# TOP.net
KiCad netlist of a schematic drawn in Altium Designer
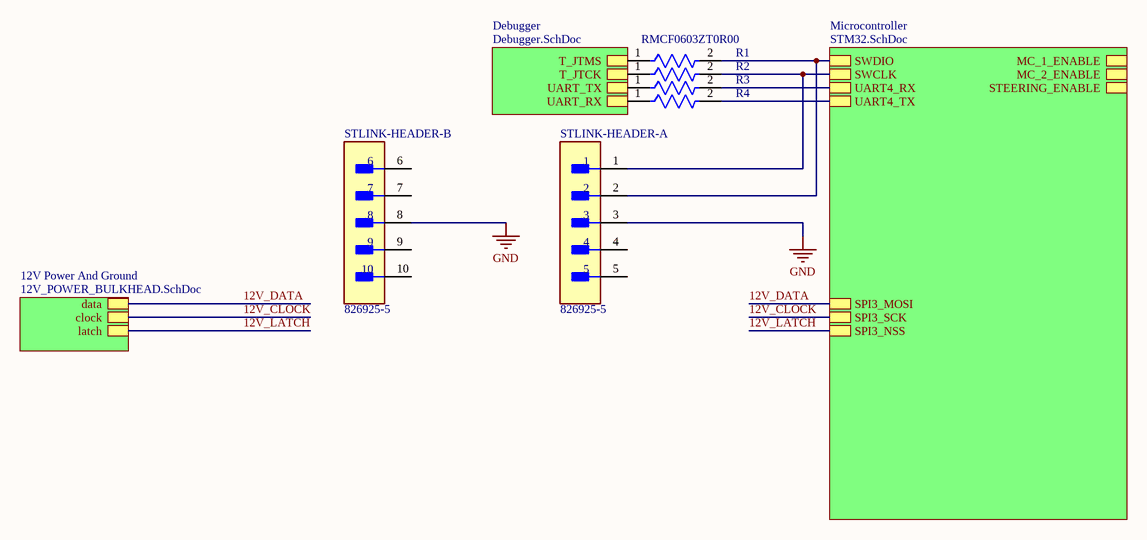
[diagram p0: TOP.SchDoc]

(export (version "E")
  (design (tool "Eeschema 10.0.6"))
  (components
    (comp (ref "R1")
      (value "RMCF0603ZT0R00")
      (footprint "FP-RMCF0603-MFG")
      (description "RES 0 OHM JUMPER 1/10W 0603")
      (fields
        (field (name "OCTOPART") "https://octopart.com/rmcf0603zt0r00-stackpole+electronics-19213618")
        (field (name "MANUFACTURER") "Stackpole")
      )
      (libsource (lib "Altium Content Vault") (part "1029c3af85768c4190bb7ad29bc67b5"))
    )
    (comp (ref "R2")
      (value "RMCF0603ZT0R00")
      (footprint "FP-RMCF0603-MFG")
      (description "RES 0 OHM JUMPER 1/10W 0603")
      (fields
        (field (name "OCTOPART") "https://octopart.com/rmcf0603zt0r00-stackpole+electronics-19213618")
        (field (name "MANUFACTURER") "Stackpole")
      )
      (libsource (lib "Altium Content Vault") (part "1029c3af85768c4190bb7ad29bc67b5"))
    )
    (comp (ref "R3")
      (value "RMCF0603ZT0R00")
      (footprint "FP-RMCF0603-MFG")
      (description "RES 0 OHM JUMPER 1/10W 0603")
      (fields
        (field (name "OCTOPART") "https://octopart.com/rmcf0603zt0r00-stackpole+electronics-19213618")
        (field (name "MANUFACTURER") "Stackpole")
      )
      (libsource (lib "Altium Content Vault") (part "1029c3af85768c4190bb7ad29bc67b5"))
    )
    (comp (ref "R4")
      (value "RMCF0603ZT0R00")
      (footprint "FP-RMCF0603-MFG")
      (description "RES 0 OHM JUMPER 1/10W 0603")
      (fields
        (field (name "OCTOPART") "https://octopart.com/rmcf0603zt0r00-stackpole+electronics-19213618")
        (field (name "MANUFACTURER") "Stackpole")
      )
      (libsource (lib "Altium Content Vault") (part "1029c3af85768c4190bb7ad29bc67b5"))
    )
    (comp (ref "STLINK-HEADER-")
      (value "826925-5")
      (footprint "FP-826925-5-MFG")
      (description "CONN HEADER VERT 10POS 2.54MM")
      (fields
        (field (name "OCTOPART") "https://octopart.com/826925-5-te+connectivity-41836231")
        (field (name "MANUFACTURER") "TE Connectivity")
      )
      (libsource (lib "Altium Content Vault") (part "de255ff815dec4fe6d5caee7def00c9"))
    )
  )
  (nets
    (net (code "7") (name "/SWCLK") (class "Default")
      (node (ref "R2") (pin "2") (pinfunction "2_2") (pintype "passive"))
      (node (ref "STLINK-HEADER-") (pin "1") (pinfunction "1_1") (pintype "passive"))
    )
    (net (code "8") (name "/SWDIO") (class "Default")
      (node (ref "R1") (pin "2") (pinfunction "2_2") (pintype "passive"))
      (node (ref "STLINK-HEADER-") (pin "2") (pinfunction "2_2") (pintype "passive"))
    )
    (net (code "9") (name "/T_JTCK") (class "Default")
      (node (ref "R2") (pin "1") (pinfunction "1_1") (pintype "passive"))
    )
    (net (code "10") (name "/T_JTMS") (class "Default")
      (node (ref "R1") (pin "1") (pinfunction "1_1") (pintype "passive"))
    )
    (net (code "11") (name "/UART4_RX") (class "Default")
      (node (ref "R3") (pin "2") (pinfunction "2_2") (pintype "passive"))
    )
    (net (code "12") (name "/UART4_TX") (class "Default")
      (node (ref "R4") (pin "2") (pinfunction "2_2") (pintype "passive"))
    )
    (net (code "13") (name "/UART_RX") (class "Default")
      (node (ref "R4") (pin "1") (pinfunction "1_1") (pintype "passive"))
    )
    (net (code "14") (name "/UART_TX") (class "Default")
      (node (ref "R3") (pin "1") (pinfunction "1_1") (pintype "passive"))
    )
    (net (code "15") (name "GND") (class "Default")
      (node (ref "STLINK-HEADER-") (pin "3") (pinfunction "3_3") (pintype "passive"))
      (node (ref "STLINK-HEADER-") (pin "8") (pinfunction "8_8") (pintype "passive"))
    )
    (net (code "16") (name "unconnected-(STLINK-HEADER--Pad4)") (class "Default")
      (node (ref "STLINK-HEADER-") (pin "4") (pinfunction "4_4") (pintype "passive"))
    )
    (net (code "17") (name "unconnected-(STLINK-HEADER--Pad5)") (class "Default")
      (node (ref "STLINK-HEADER-") (pin "5") (pinfunction "5_5") (pintype "passive"))
    )
    (net (code "18") (name "unconnected-(STLINK-HEADER--Pad6)") (class "Default")
      (node (ref "STLINK-HEADER-") (pin "6") (pinfunction "6_6") (pintype "passive"))
    )
    (net (code "19") (name "unconnected-(STLINK-HEADER--Pad7)") (class "Default")
      (node (ref "STLINK-HEADER-") (pin "7") (pinfunction "7_7") (pintype "passive"))
    )
    (net (code "20") (name "unconnected-(STLINK-HEADER--Pad9)") (class "Default")
      (node (ref "STLINK-HEADER-") (pin "9") (pinfunction "9_9") (pintype "passive"))
    )
    (net (code "21") (name "unconnected-(STLINK-HEADER--Pad10)") (class "Default")
      (node (ref "STLINK-HEADER-") (pin "10") (pinfunction "10_10") (pintype "passive"))
    )
  )
)
